# Schema.net
KiCad netlist of a schematic drawn in EasyEDA
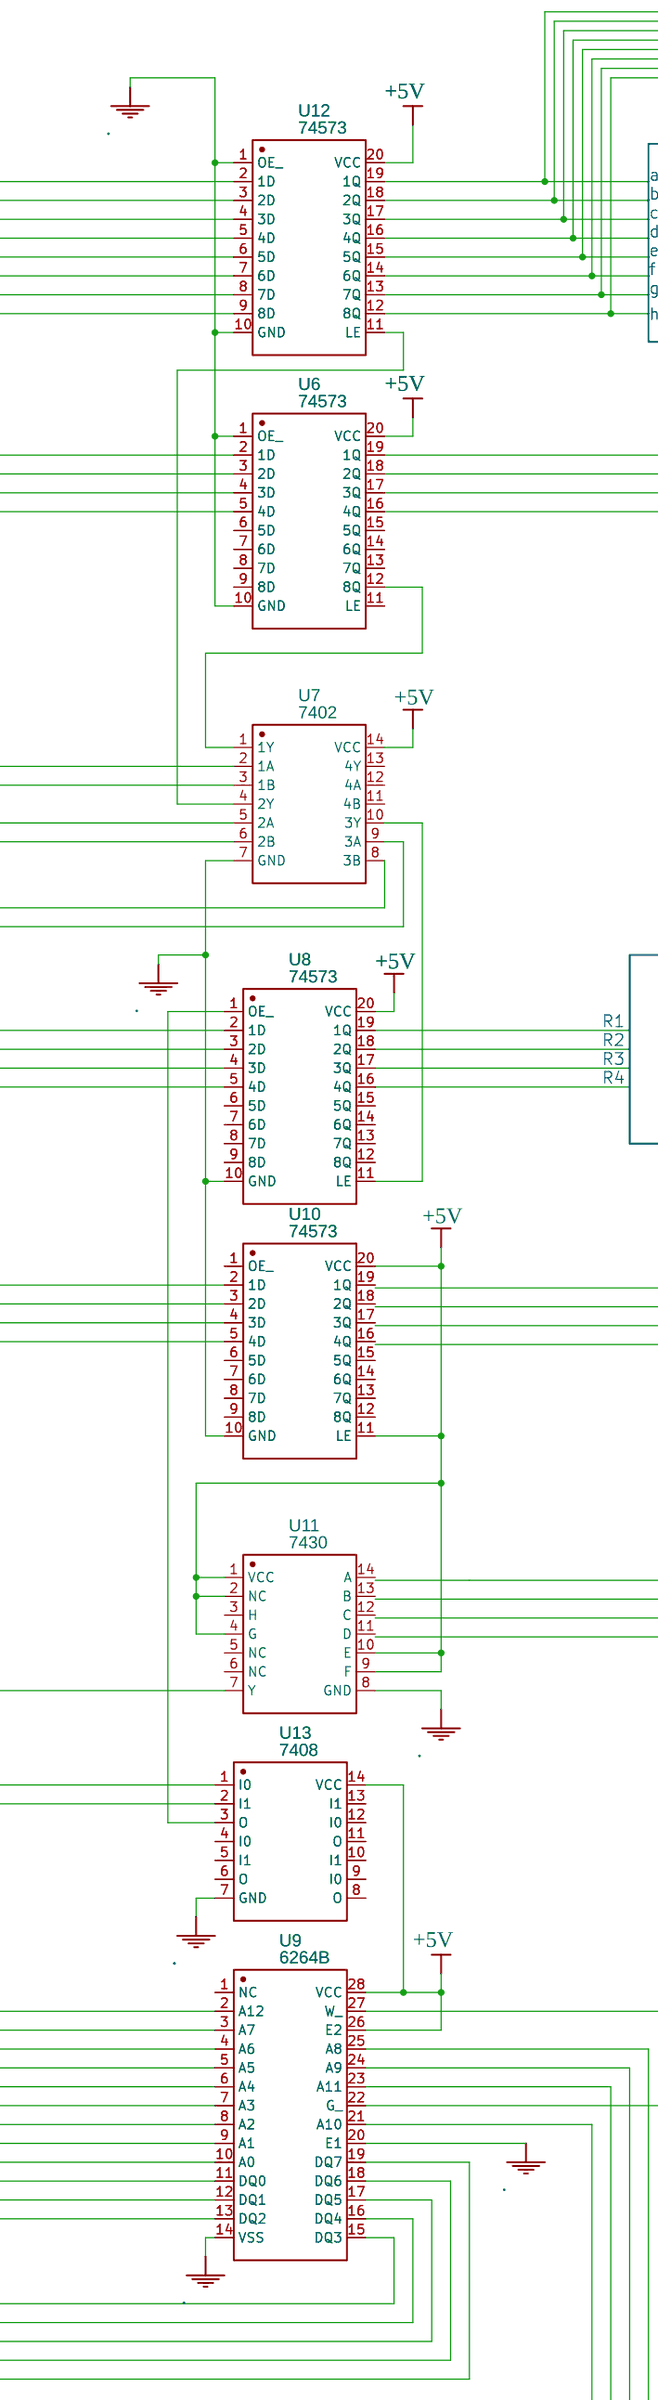
[diagram p0: schematic sheet]

(export (version "E")
  (design (tool "Eeschema 10.0.6"))
  (components
    (comp (ref "U6")
      (value "74573")
      (fields (field (name "BOM_Manufacturer Part") "?"))
      (libsource (lib "") (part "Unknown_1135_275"))
    )
    (comp (ref "U7")
      (value "7402")
      (fields (field (name "BOM_Manufacturer Part") "?"))
      (libsource (lib "") (part "Unknown_1135_425"))
    )
    (comp (ref "U8")
      (value "74573")
      (fields (field (name "BOM_Manufacturer Part") "?"))
      (libsource (lib "") (part "Unknown_1130_580"))
    )
    (comp (ref "U9")
      (value "6264B")
      (fields (field (name "BOM_Manufacturer Part") "?"))
      (libsource (lib "") (part "Unknown_1125_1120"))
    )
    (comp (ref "U10")
      (value "74573")
      (fields (field (name "BOM_Manufacturer Part") "?"))
      (libsource (lib "") (part "Unknown_1130_715"))
    )
    (comp (ref "U11")
      (value "7430")
      (fields
        (field (name "BOM_Manufacturer Part") "74HCT164D,652")
        (field (name "BOM_Supplier Part") "C5971")
      )
      (libsource (lib "") (part "Unknown_1130_865"))
    )
    (comp (ref "U12")
      (value "74573")
      (fields (field (name "BOM_Manufacturer Part") "?"))
      (libsource (lib "") (part "Unknown_1135_130"))
    )
    (comp (ref "U13")
      (value "7408")
      (fields (field (name "BOM_Manufacturer Part") "?"))
      (libsource (lib "") (part "Unknown_1125_975"))
    )
  )
  (nets
    (net (code "1") (name "+5V") (class "Default")
      (node (ref "U10") (pin "11") (pinfunction "LE_11") (pintype "unspecified"))
      (node (ref "U10") (pin "20") (pinfunction "VCC_20") (pintype "unspecified"))
      (node (ref "U11") (pin "1") (pinfunction "VCC_1") (pintype "unspecified"))
      (node (ref "U11") (pin "10") (pinfunction "E_10") (pintype "unspecified"))
      (node (ref "U11") (pin "2") (pinfunction "NC_2") (pintype "unspecified"))
      (node (ref "U11") (pin "4") (pinfunction "G_4") (pintype "unspecified"))
      (node (ref "U11") (pin "9") (pinfunction "F_9") (pintype "unspecified"))
      (node (ref "U12") (pin "20") (pinfunction "VCC_20") (pintype "unspecified"))
      (node (ref "U13") (pin "14") (pinfunction "VCC_14") (pintype "unspecified"))
      (node (ref "U6") (pin "20") (pinfunction "VCC_20") (pintype "unspecified"))
      (node (ref "U7") (pin "14") (pinfunction "VCC_14") (pintype "unspecified"))
      (node (ref "U8") (pin "20") (pinfunction "VCC_20") (pintype "unspecified"))
      (node (ref "U9") (pin "26") (pinfunction "E2_26") (pintype "unspecified"))
      (node (ref "U9") (pin "28") (pinfunction "VCC_28") (pintype "unspecified"))
    )
    (net (code "2") (name ".") (class "Default")
      (node (ref "U10") (pin "10") (pinfunction "GND_10") (pintype "unspecified"))
      (node (ref "U11") (pin "8") (pinfunction "GND_8") (pintype "unspecified"))
      (node (ref "U12") (pin "1") (pinfunction "OE__1") (pintype "unspecified"))
      (node (ref "U12") (pin "10") (pinfunction "GND_10") (pintype "unspecified"))
      (node (ref "U13") (pin "7") (pinfunction "GND_7") (pintype "unspecified"))
      (node (ref "U6") (pin "1") (pinfunction "OE__1") (pintype "unspecified"))
      (node (ref "U6") (pin "10") (pinfunction "GND_10") (pintype "unspecified"))
      (node (ref "U7") (pin "7") (pinfunction "GND_7") (pintype "unspecified"))
      (node (ref "U8") (pin "10") (pinfunction "GND_10") (pintype "unspecified"))
      (node (ref "U9") (pin "14") (pinfunction "VSS_14") (pintype "unspecified"))
      (node (ref "U9") (pin "20") (pinfunction "E1_20") (pintype "unspecified"))
    )
    (net (code "3") (name "Net-(U6-8Q)") (class "Default")
      (node (ref "U6") (pin "12") (pinfunction "8Q_12") (pintype "unspecified"))
      (node (ref "U7") (pin "1") (pinfunction "1Y_1") (pintype "unspecified"))
    )
    (net (code "4") (name "Net-(U7-1A)") (class "Default")
      (node (ref "U7") (pin "2") (pinfunction "1A_2") (pintype "unspecified"))
      (node (ref "U7") (pin "5") (pinfunction "2A_5") (pintype "unspecified"))
      (node (ref "U7") (pin "9") (pinfunction "3A_9") (pintype "unspecified"))
      (node (ref "U9") (pin "10") (pinfunction "A0_10") (pintype "unspecified"))
      (node (ref "U9") (pin "2") (pinfunction "A12_2") (pintype "unspecified"))
      (node (ref "U9") (pin "21") (pinfunction "A10_21") (pintype "unspecified"))
      (node (ref "U9") (pin "23") (pinfunction "A11_23") (pintype "unspecified"))
      (node (ref "U9") (pin "24") (pinfunction "A9_24") (pintype "unspecified"))
      (node (ref "U9") (pin "25") (pinfunction "A8_25") (pintype "unspecified"))
      (node (ref "U9") (pin "3") (pinfunction "A7_3") (pintype "unspecified"))
      (node (ref "U9") (pin "4") (pinfunction "A6_4") (pintype "unspecified"))
      (node (ref "U9") (pin "5") (pinfunction "A5_5") (pintype "unspecified"))
      (node (ref "U9") (pin "6") (pinfunction "A4_6") (pintype "unspecified"))
      (node (ref "U9") (pin "7") (pinfunction "A3_7") (pintype "unspecified"))
      (node (ref "U9") (pin "8") (pinfunction "A2_8") (pintype "unspecified"))
      (node (ref "U9") (pin "9") (pinfunction "A1_9") (pintype "unspecified"))
    )
    (net (code "5") (name "Net-(U7-1B)") (class "Default")
      (node (ref "U7") (pin "3") (pinfunction "1B_3") (pintype "unspecified"))
      (node (ref "U7") (pin "6") (pinfunction "2B_6") (pintype "unspecified"))
      (node (ref "U7") (pin "8") (pinfunction "3B_8") (pintype "unspecified"))
    )
    (net (code "6") (name "Net-(U7-3Y)") (class "Default")
      (node (ref "U7") (pin "10") (pinfunction "3Y_10") (pintype "unspecified"))
      (node (ref "U8") (pin "11") (pinfunction "LE_11") (pintype "unspecified"))
    )
    (net (code "7") (name "Net-(U8-OE_)") (class "Default")
      (node (ref "U13") (pin "3") (pinfunction "O_3") (pintype "unspecified"))
      (node (ref "U8") (pin "1") (pinfunction "OE__1") (pintype "unspecified"))
    )
    (net (code "8") (name "Net-(U10-1D)") (class "Default")
      (node (ref "U10") (pin "2") (pinfunction "1D_2") (pintype "unspecified"))
      (node (ref "U10") (pin "3") (pinfunction "2D_3") (pintype "unspecified"))
      (node (ref "U10") (pin "4") (pinfunction "3D_4") (pintype "unspecified"))
      (node (ref "U10") (pin "5") (pinfunction "4D_5") (pintype "unspecified"))
      (node (ref "U12") (pin "2") (pinfunction "1D_2") (pintype "unspecified"))
      (node (ref "U12") (pin "3") (pinfunction "2D_3") (pintype "unspecified"))
      (node (ref "U12") (pin "4") (pinfunction "3D_4") (pintype "unspecified"))
      (node (ref "U12") (pin "5") (pinfunction "4D_5") (pintype "unspecified"))
      (node (ref "U12") (pin "6") (pinfunction "5D_6") (pintype "unspecified"))
      (node (ref "U12") (pin "7") (pinfunction "6D_7") (pintype "unspecified"))
      (node (ref "U12") (pin "8") (pinfunction "7D_8") (pintype "unspecified"))
      (node (ref "U12") (pin "9") (pinfunction "8D_9") (pintype "unspecified"))
      (node (ref "U6") (pin "2") (pinfunction "1D_2") (pintype "unspecified"))
      (node (ref "U6") (pin "3") (pinfunction "2D_3") (pintype "unspecified"))
      (node (ref "U6") (pin "4") (pinfunction "3D_4") (pintype "unspecified"))
      (node (ref "U6") (pin "5") (pinfunction "4D_5") (pintype "unspecified"))
      (node (ref "U8") (pin "2") (pinfunction "1D_2") (pintype "unspecified"))
      (node (ref "U8") (pin "3") (pinfunction "2D_3") (pintype "unspecified"))
      (node (ref "U8") (pin "4") (pinfunction "3D_4") (pintype "unspecified"))
      (node (ref "U8") (pin "5") (pinfunction "4D_5") (pintype "unspecified"))
      (node (ref "U9") (pin "11") (pinfunction "DQ0_11") (pintype "unspecified"))
      (node (ref "U9") (pin "12") (pinfunction "DQ1_12") (pintype "unspecified"))
      (node (ref "U9") (pin "13") (pinfunction "DQ2_13") (pintype "unspecified"))
      (node (ref "U9") (pin "15") (pinfunction "DQ3_15") (pintype "unspecified"))
      (node (ref "U9") (pin "16") (pinfunction "DQ4_16") (pintype "unspecified"))
      (node (ref "U9") (pin "17") (pinfunction "DQ5_17") (pintype "unspecified"))
      (node (ref "U9") (pin "18") (pinfunction "DQ6_18") (pintype "unspecified"))
      (node (ref "U9") (pin "19") (pinfunction "DQ7_19") (pintype "unspecified"))
    )
    (net (code "9") (name "Net-(U12-LE)") (class "Default")
      (node (ref "U12") (pin "11") (pinfunction "LE_11") (pintype "unspecified"))
      (node (ref "U7") (pin "4") (pinfunction "2Y_4") (pintype "unspecified"))
    )
    (net (code "10") (name "unconnected-(U6-1Q-Pad19)") (class "Default")
      (node (ref "U6") (pin "19") (pinfunction "1Q_19") (pintype "unspecified"))
    )
    (net (code "11") (name "unconnected-(U6-2Q-Pad18)") (class "Default")
      (node (ref "U6") (pin "18") (pinfunction "2Q_18") (pintype "unspecified"))
    )
    (net (code "12") (name "unconnected-(U6-3Q-Pad17)") (class "Default")
      (node (ref "U6") (pin "17") (pinfunction "3Q_17") (pintype "unspecified"))
    )
    (net (code "13") (name "unconnected-(U6-4Q-Pad16)") (class "Default")
      (node (ref "U6") (pin "16") (pinfunction "4Q_16") (pintype "unspecified"))
    )
    (net (code "14") (name "unconnected-(U6-5D-Pad6)") (class "Default")
      (node (ref "U6") (pin "6") (pinfunction "5D_6") (pintype "unspecified"))
    )
    (net (code "15") (name "unconnected-(U6-5Q-Pad15)") (class "Default")
      (node (ref "U6") (pin "15") (pinfunction "5Q_15") (pintype "unspecified"))
    )
    (net (code "16") (name "unconnected-(U6-6D-Pad7)") (class "Default")
      (node (ref "U6") (pin "7") (pinfunction "6D_7") (pintype "unspecified"))
    )
    (net (code "17") (name "unconnected-(U6-6Q-Pad14)") (class "Default")
      (node (ref "U6") (pin "14") (pinfunction "6Q_14") (pintype "unspecified"))
    )
    (net (code "18") (name "unconnected-(U6-7D-Pad8)") (class "Default")
      (node (ref "U6") (pin "8") (pinfunction "7D_8") (pintype "unspecified"))
    )
    (net (code "19") (name "unconnected-(U6-7Q-Pad13)") (class "Default")
      (node (ref "U6") (pin "13") (pinfunction "7Q_13") (pintype "unspecified"))
    )
    (net (code "20") (name "unconnected-(U6-8D-Pad9)") (class "Default")
      (node (ref "U6") (pin "9") (pinfunction "8D_9") (pintype "unspecified"))
    )
    (net (code "21") (name "unconnected-(U6-LE-Pad11)") (class "Default")
      (node (ref "U6") (pin "11") (pinfunction "LE_11") (pintype "unspecified"))
    )
    (net (code "22") (name "unconnected-(U7-4A-Pad12)") (class "Default")
      (node (ref "U7") (pin "12") (pinfunction "4A_12") (pintype "unspecified"))
    )
    (net (code "23") (name "unconnected-(U7-4B-Pad11)") (class "Default")
      (node (ref "U7") (pin "11") (pinfunction "4B_11") (pintype "unspecified"))
    )
    (net (code "24") (name "unconnected-(U7-4Y-Pad13)") (class "Default")
      (node (ref "U7") (pin "13") (pinfunction "4Y_13") (pintype "unspecified"))
    )
    (net (code "25") (name "unconnected-(U8-1Q-Pad19)") (class "Default")
      (node (ref "U8") (pin "19") (pinfunction "1Q_19") (pintype "unspecified"))
    )
    (net (code "26") (name "unconnected-(U8-2Q-Pad18)") (class "Default")
      (node (ref "U8") (pin "18") (pinfunction "2Q_18") (pintype "unspecified"))
    )
    (net (code "27") (name "unconnected-(U8-3Q-Pad17)") (class "Default")
      (node (ref "U8") (pin "17") (pinfunction "3Q_17") (pintype "unspecified"))
    )
    (net (code "28") (name "unconnected-(U8-4Q-Pad16)") (class "Default")
      (node (ref "U8") (pin "16") (pinfunction "4Q_16") (pintype "unspecified"))
    )
    (net (code "29") (name "unconnected-(U8-5D-Pad6)") (class "Default")
      (node (ref "U8") (pin "6") (pinfunction "5D_6") (pintype "unspecified"))
    )
    (net (code "30") (name "unconnected-(U8-5Q-Pad15)") (class "Default")
      (node (ref "U8") (pin "15") (pinfunction "5Q_15") (pintype "unspecified"))
    )
    (net (code "31") (name "unconnected-(U8-6D-Pad7)") (class "Default")
      (node (ref "U8") (pin "7") (pinfunction "6D_7") (pintype "unspecified"))
    )
    (net (code "32") (name "unconnected-(U8-6Q-Pad14)") (class "Default")
      (node (ref "U8") (pin "14") (pinfunction "6Q_14") (pintype "unspecified"))
    )
    (net (code "33") (name "unconnected-(U8-7D-Pad8)") (class "Default")
      (node (ref "U8") (pin "8") (pinfunction "7D_8") (pintype "unspecified"))
    )
    (net (code "34") (name "unconnected-(U8-7Q-Pad13)") (class "Default")
      (node (ref "U8") (pin "13") (pinfunction "7Q_13") (pintype "unspecified"))
    )
    (net (code "35") (name "unconnected-(U8-8D-Pad9)") (class "Default")
      (node (ref "U8") (pin "9") (pinfunction "8D_9") (pintype "unspecified"))
    )
    (net (code "36") (name "unconnected-(U8-8Q-Pad12)") (class "Default")
      (node (ref "U8") (pin "12") (pinfunction "8Q_12") (pintype "unspecified"))
    )
    (net (code "37") (name "unconnected-(U9-G_-Pad22)") (class "Default")
      (node (ref "U9") (pin "22") (pinfunction "G__22") (pintype "unspecified"))
    )
    (net (code "38") (name "unconnected-(U9-NC-Pad1)") (class "Default")
      (node (ref "U9") (pin "1") (pinfunction "NC_1") (pintype "unspecified"))
    )
    (net (code "39") (name "unconnected-(U9-W_-Pad27)") (class "Default")
      (node (ref "U9") (pin "27") (pinfunction "W__27") (pintype "unspecified"))
    )
    (net (code "40") (name "unconnected-(U10-1Q-Pad19)") (class "Default")
      (node (ref "U10") (pin "19") (pinfunction "1Q_19") (pintype "unspecified"))
    )
    (net (code "41") (name "unconnected-(U10-2Q-Pad18)") (class "Default")
      (node (ref "U10") (pin "18") (pinfunction "2Q_18") (pintype "unspecified"))
    )
    (net (code "42") (name "unconnected-(U10-3Q-Pad17)") (class "Default")
      (node (ref "U10") (pin "17") (pinfunction "3Q_17") (pintype "unspecified"))
    )
    (net (code "43") (name "unconnected-(U10-4Q-Pad16)") (class "Default")
      (node (ref "U10") (pin "16") (pinfunction "4Q_16") (pintype "unspecified"))
    )
    (net (code "44") (name "unconnected-(U10-5D-Pad6)") (class "Default")
      (node (ref "U10") (pin "6") (pinfunction "5D_6") (pintype "unspecified"))
    )
    (net (code "45") (name "unconnected-(U10-5Q-Pad15)") (class "Default")
      (node (ref "U10") (pin "15") (pinfunction "5Q_15") (pintype "unspecified"))
    )
    (net (code "46") (name "unconnected-(U10-6D-Pad7)") (class "Default")
      (node (ref "U10") (pin "7") (pinfunction "6D_7") (pintype "unspecified"))
    )
    (net (code "47") (name "unconnected-(U10-6Q-Pad14)") (class "Default")
      (node (ref "U10") (pin "14") (pinfunction "6Q_14") (pintype "unspecified"))
    )
    (net (code "48") (name "unconnected-(U10-7D-Pad8)") (class "Default")
      (node (ref "U10") (pin "8") (pinfunction "7D_8") (pintype "unspecified"))
    )
    (net (code "49") (name "unconnected-(U10-7Q-Pad13)") (class "Default")
      (node (ref "U10") (pin "13") (pinfunction "7Q_13") (pintype "unspecified"))
    )
    (net (code "50") (name "unconnected-(U10-8D-Pad9)") (class "Default")
      (node (ref "U10") (pin "9") (pinfunction "8D_9") (pintype "unspecified"))
    )
    (net (code "51") (name "unconnected-(U10-8Q-Pad12)") (class "Default")
      (node (ref "U10") (pin "12") (pinfunction "8Q_12") (pintype "unspecified"))
    )
    (net (code "52") (name "unconnected-(U10-OE_-Pad1)") (class "Default")
      (node (ref "U10") (pin "1") (pinfunction "OE__1") (pintype "unspecified"))
    )
    (net (code "53") (name "unconnected-(U11-A-Pad14)") (class "Default")
      (node (ref "U11") (pin "14") (pinfunction "A_14") (pintype "unspecified"))
    )
    (net (code "54") (name "unconnected-(U11-B-Pad13)") (class "Default")
      (node (ref "U11") (pin "13") (pinfunction "B_13") (pintype "unspecified"))
    )
    (net (code "55") (name "unconnected-(U11-C-Pad12)") (class "Default")
      (node (ref "U11") (pin "12") (pinfunction "C_12") (pintype "unspecified"))
    )
    (net (code "56") (name "unconnected-(U11-D-Pad11)") (class "Default")
      (node (ref "U11") (pin "11") (pinfunction "D_11") (pintype "unspecified"))
    )
    (net (code "57") (name "unconnected-(U11-H-Pad3)") (class "Default")
      (node (ref "U11") (pin "3") (pinfunction "H_3") (pintype "unspecified"))
    )
    (net (code "58") (name "unconnected-(U11-NC-Pad5)") (class "Default")
      (node (ref "U11") (pin "5") (pinfunction "NC_5") (pintype "unspecified"))
    )
    (net (code "59") (name "unconnected-(U11-NC-Pad6)") (class "Default")
      (node (ref "U11") (pin "6") (pinfunction "NC_6") (pintype "unspecified"))
    )
    (net (code "60") (name "unconnected-(U11-Y-Pad7)") (class "Default")
      (node (ref "U11") (pin "7") (pinfunction "Y_7") (pintype "unspecified"))
    )
    (net (code "61") (name "unconnected-(U12-1Q-Pad19)") (class "Default")
      (node (ref "U12") (pin "19") (pinfunction "1Q_19") (pintype "unspecified"))
    )
    (net (code "62") (name "unconnected-(U12-2Q-Pad18)") (class "Default")
      (node (ref "U12") (pin "18") (pinfunction "2Q_18") (pintype "unspecified"))
    )
    (net (code "63") (name "unconnected-(U12-3Q-Pad17)") (class "Default")
      (node (ref "U12") (pin "17") (pinfunction "3Q_17") (pintype "unspecified"))
    )
    (net (code "64") (name "unconnected-(U12-4Q-Pad16)") (class "Default")
      (node (ref "U12") (pin "16") (pinfunction "4Q_16") (pintype "unspecified"))
    )
    (net (code "65") (name "unconnected-(U12-5Q-Pad15)") (class "Default")
      (node (ref "U12") (pin "15") (pinfunction "5Q_15") (pintype "unspecified"))
    )
    (net (code "66") (name "unconnected-(U12-6Q-Pad14)") (class "Default")
      (node (ref "U12") (pin "14") (pinfunction "6Q_14") (pintype "unspecified"))
    )
    (net (code "67") (name "unconnected-(U12-7Q-Pad13)") (class "Default")
      (node (ref "U12") (pin "13") (pinfunction "7Q_13") (pintype "unspecified"))
    )
    (net (code "68") (name "unconnected-(U12-8Q-Pad12)") (class "Default")
      (node (ref "U12") (pin "12") (pinfunction "8Q_12") (pintype "unspecified"))
    )
    (net (code "69") (name "unconnected-(U13-I0-Pad1)") (class "Default")
      (node (ref "U13") (pin "1") (pinfunction "I0_1") (pintype "unspecified"))
    )
    (net (code "70") (name "unconnected-(U13-I0-Pad4)") (class "Default")
      (node (ref "U13") (pin "4") (pinfunction "I0_4") (pintype "unspecified"))
    )
    (net (code "71") (name "unconnected-(U13-I0-Pad9)") (class "Default")
      (node (ref "U13") (pin "9") (pinfunction "I0_9") (pintype "unspecified"))
    )
    (net (code "72") (name "unconnected-(U13-I0-Pad12)") (class "Default")
      (node (ref "U13") (pin "12") (pinfunction "I0_12") (pintype "unspecified"))
    )
    (net (code "73") (name "unconnected-(U13-I1-Pad2)") (class "Default")
      (node (ref "U13") (pin "2") (pinfunction "I1_2") (pintype "unspecified"))
    )
    (net (code "74") (name "unconnected-(U13-I1-Pad5)") (class "Default")
      (node (ref "U13") (pin "5") (pinfunction "I1_5") (pintype "unspecified"))
    )
    (net (code "75") (name "unconnected-(U13-I1-Pad10)") (class "Default")
      (node (ref "U13") (pin "10") (pinfunction "I1_10") (pintype "unspecified"))
    )
    (net (code "76") (name "unconnected-(U13-I1-Pad13)") (class "Default")
      (node (ref "U13") (pin "13") (pinfunction "I1_13") (pintype "unspecified"))
    )
    (net (code "77") (name "unconnected-(U13-O-Pad6)") (class "Default")
      (node (ref "U13") (pin "6") (pinfunction "O_6") (pintype "unspecified"))
    )
    (net (code "78") (name "unconnected-(U13-O-Pad8)") (class "Default")
      (node (ref "U13") (pin "8") (pinfunction "O_8") (pintype "unspecified"))
    )
    (net (code "79") (name "unconnected-(U13-O-Pad11)") (class "Default")
      (node (ref "U13") (pin "11") (pinfunction "O_11") (pintype "unspecified"))
    )
  )
)
